# BIRDS4_-Y_panel_FM_GUARANI_v3.net
KiCad netlist of a schematic drawn in EAGLE
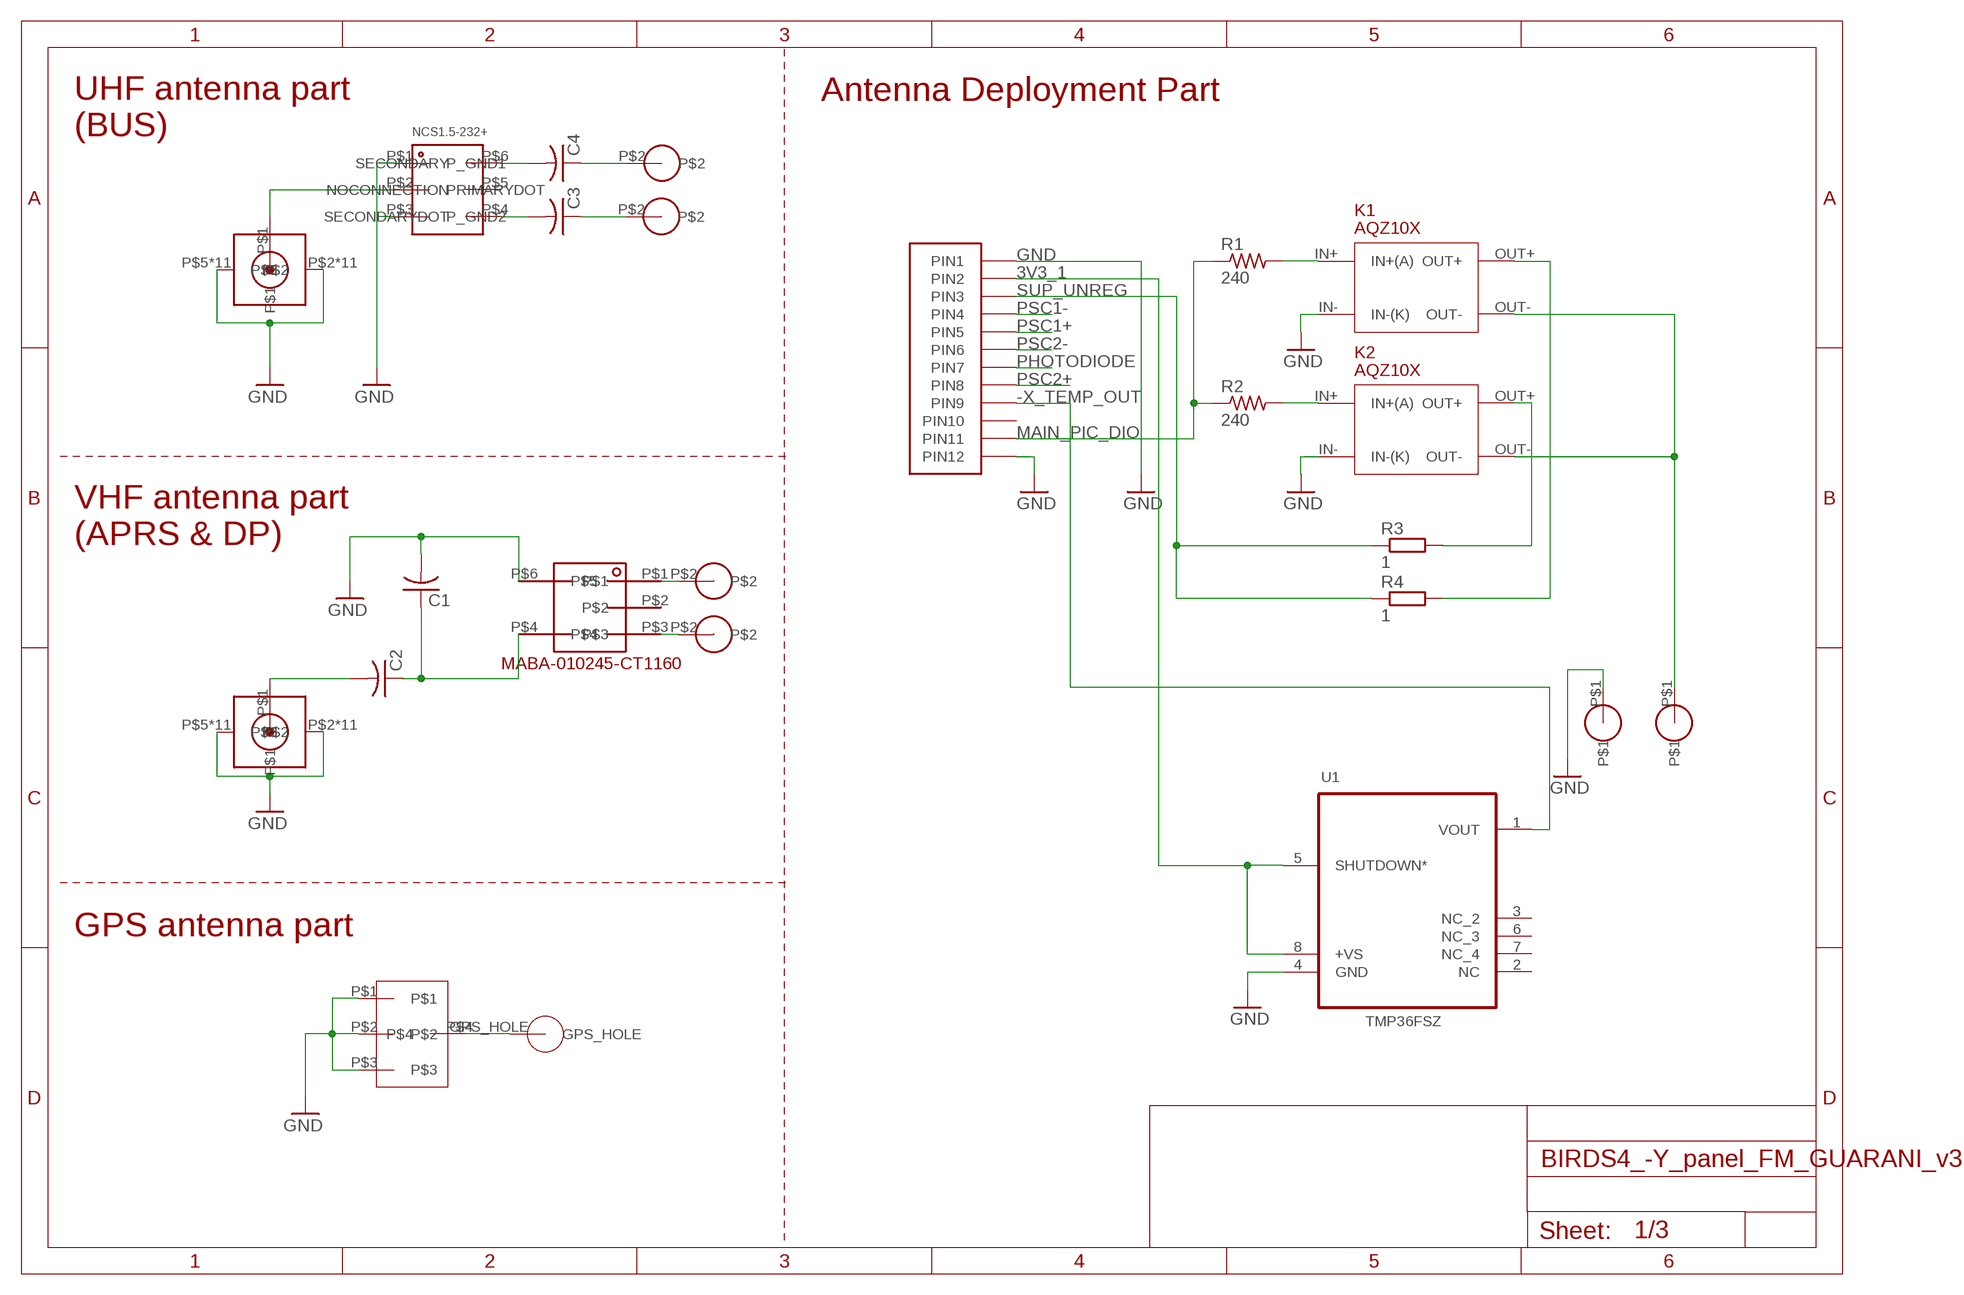
[diagram p0: schematic, sheet 1]
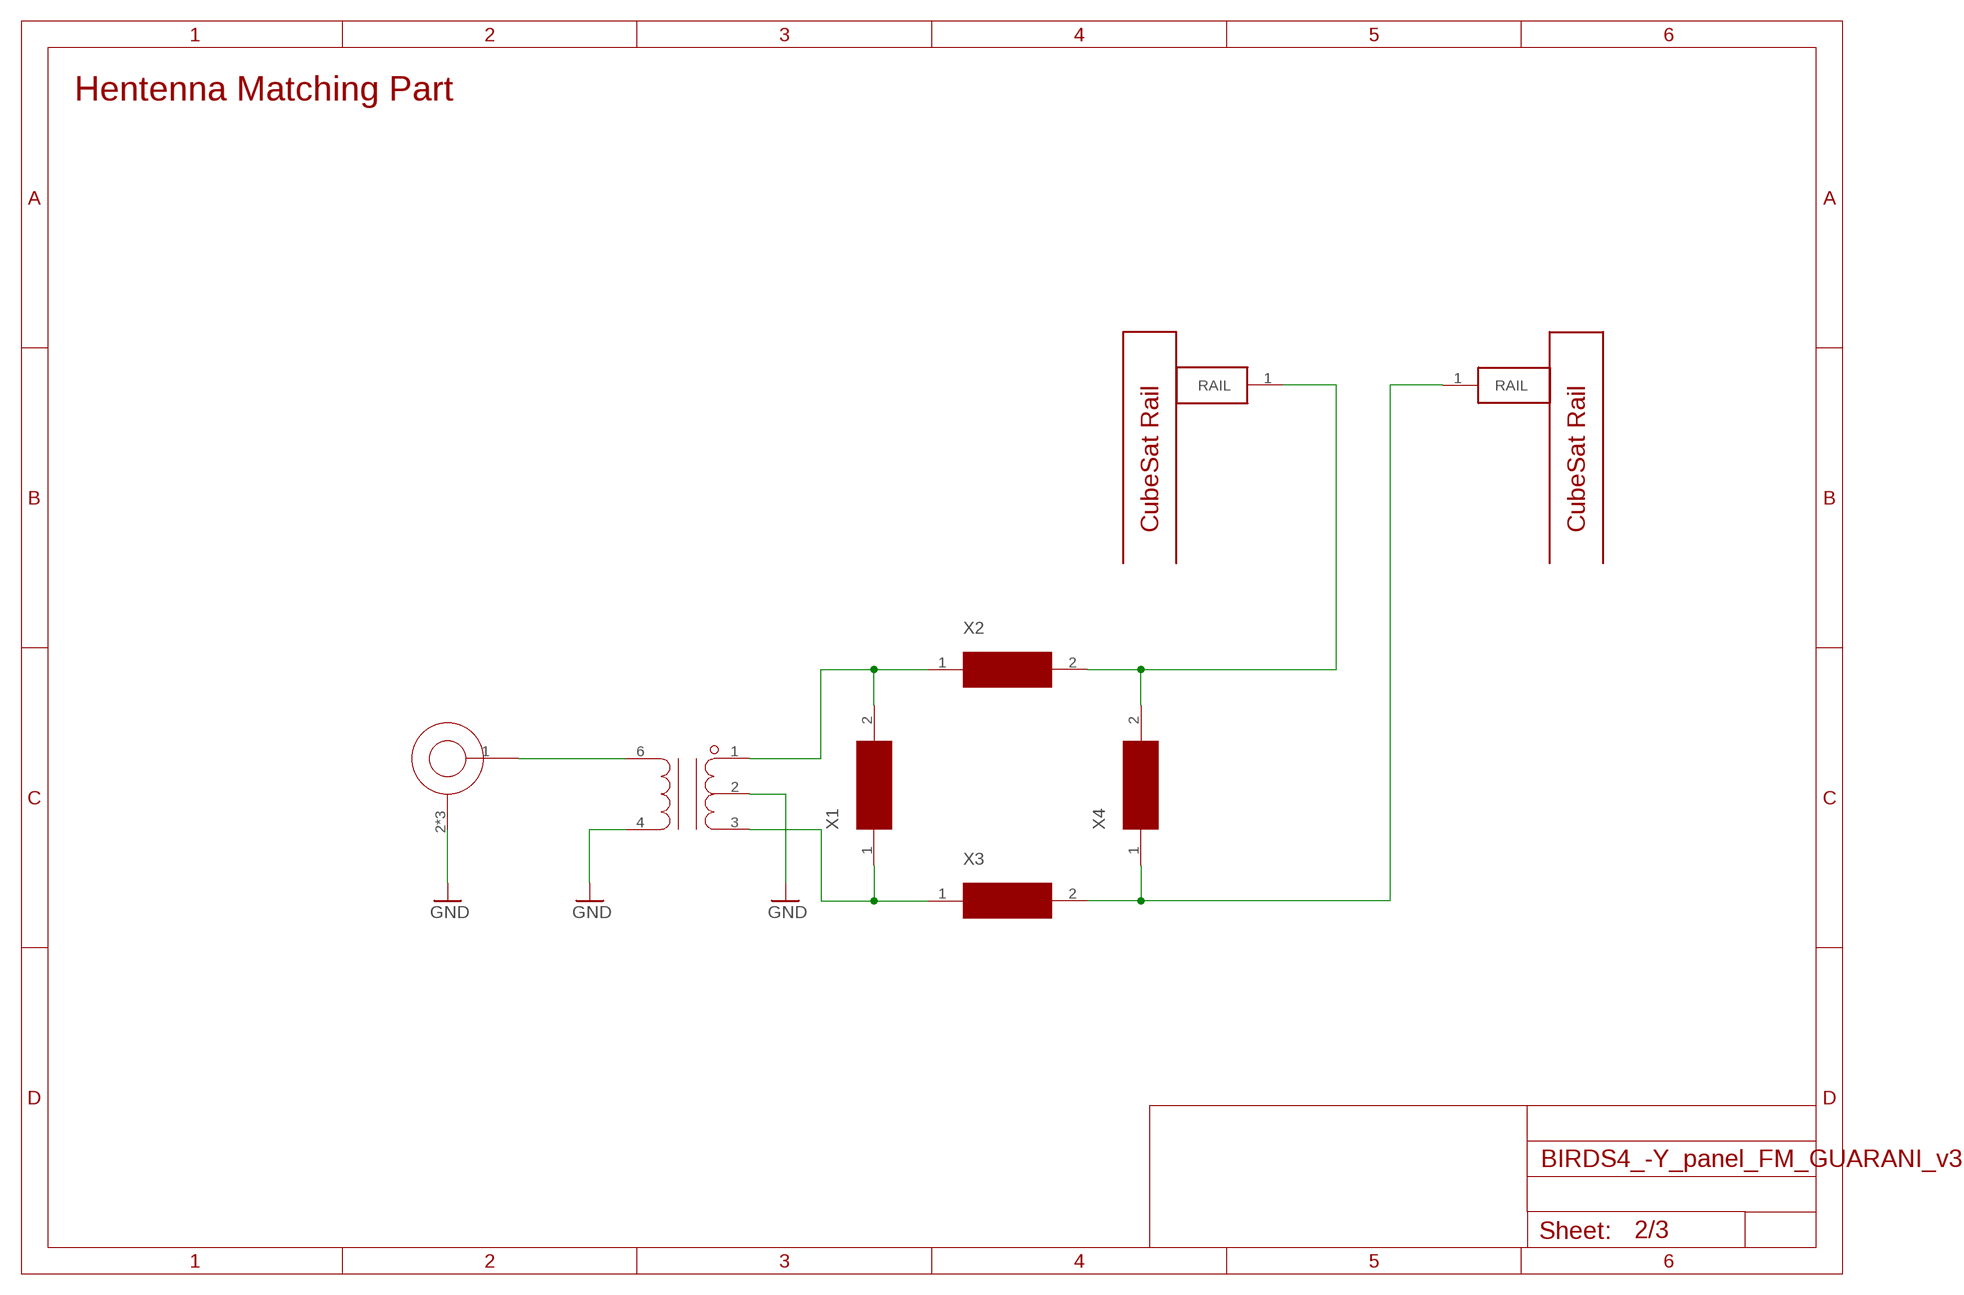
[diagram p1: schematic, sheet 2]
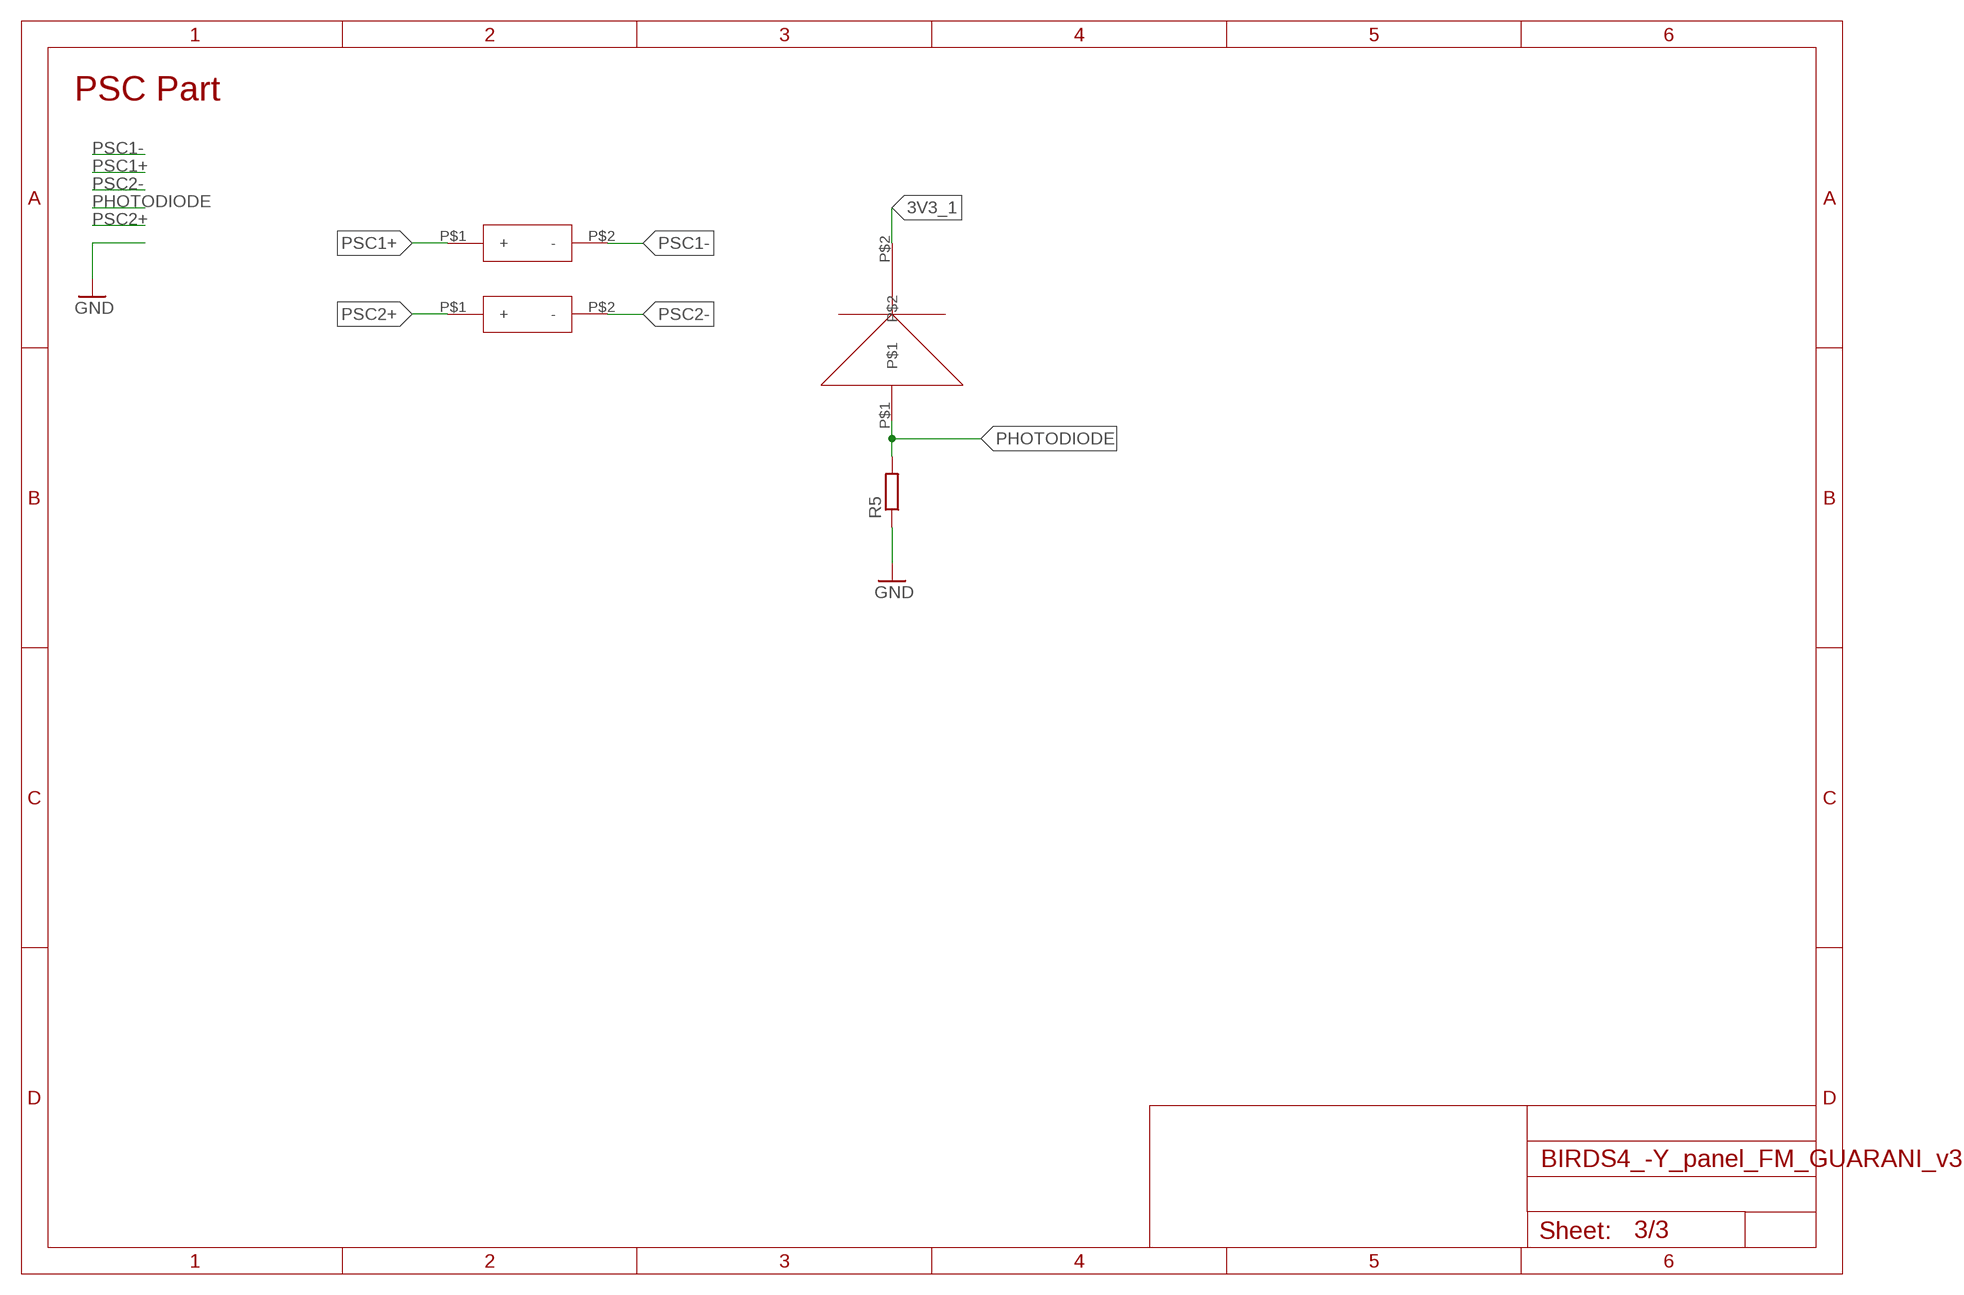
[diagram p2: schematic, sheet 3]

(export (version "E")
  (design (tool "Eeschema 10.0.6"))
  (components
    (comp (ref "C1")
      (value "C-USC1608")
      (footprint "eagle-import:C1608")
      (libsource (lib "eagle-import") (part "C-USC1608"))
    )
    (comp (ref "C2")
      (value "C-USC1608")
      (footprint "eagle-import:C1608")
      (libsource (lib "eagle-import") (part "C-USC1608"))
    )
    (comp (ref "C3")
      (value "C-USC1608")
      (footprint "eagle-import:C1608")
      (libsource (lib "eagle-import") (part "C-USC1608"))
    )
    (comp (ref "C4")
      (value "C-USC1608")
      (footprint "eagle-import:C1608")
      (libsource (lib "eagle-import") (part "C-USC1608"))
    )
    (comp (ref "HOLE1")
      (value "B4_FOR_NEW_DIPOLE")
      (footprint "eagle-import:B4_FOR_NEW_DIPOLE")
      (libsource (lib "eagle-import") (part "B4_FOR_NEW_DIPOLE"))
    )
    (comp (ref "HOLE2")
      (value "B4_FOR_NEW_DIPOLE")
      (footprint "eagle-import:B4_FOR_NEW_DIPOLE")
      (libsource (lib "eagle-import") (part "B4_FOR_NEW_DIPOLE"))
    )
    (comp (ref "HOLE7")
      (value "GPS_HOLE")
      (footprint "eagle-import:GPS_HOLE")
      (libsource (lib "eagle-import") (part "GPS_HOLE"))
    )
    (comp (ref "J1")
      (value "SMA_142_0711_301")
      (footprint "eagle-import:SMA_142_0711_301")
      (libsource (lib "eagle-import") (part "SMA_142_0711_301"))
    )
    (comp (ref "J2")
      (value "SMA_142_0711_301")
      (footprint "eagle-import:SMA_142_0711_301")
      (libsource (lib "eagle-import") (part "SMA_142_0711_301"))
    )
    (comp (ref "J3")
      (value "MMCX_GPS")
      (footprint "eagle-import:MMCX_GPS")
      (libsource (lib "eagle-import") (part "MMCX_GPS"))
    )
    (comp (ref "J5")
      (value "HEADER12PIN")
      (footprint "eagle-import:HEADER12PIN")
      (fields (field (name "SPICEPREFIX") "X"))
      (libsource (lib "eagle-import") (part "HEADER12PIN"))
    )
    (comp (ref "K1")
      (value "AQZ10X")
      (footprint "eagle-import:AQZ10X")
      (libsource (lib "eagle-import") (part "AQZ10X"))
    )
    (comp (ref "K2")
      (value "AQZ10X")
      (footprint "eagle-import:AQZ10X")
      (libsource (lib "eagle-import") (part "AQZ10X"))
    )
    (comp (ref "NCS1")
      (value "NCS1.5-232+")
      (footprint "eagle-import:NCS1.5-232+")
      (libsource (lib "eagle-import") (part "NCS1.5-232+"))
    )
    (comp (ref "R1")
      (value "240")
      (footprint "eagle-import:R0402")
      (libsource (lib "eagle-import") (part "R-US_R0402"))
    )
    (comp (ref "R2")
      (value "240")
      (footprint "eagle-import:R0402")
      (libsource (lib "eagle-import") (part "R-US_R0402"))
    )
    (comp (ref "R3")
      (value "1")
      (footprint "eagle-import:R1218")
      (libsource (lib "eagle-import") (part "R-EU_R1218"))
    )
    (comp (ref "R4")
      (value "1")
      (footprint "eagle-import:R1218")
      (libsource (lib "eagle-import") (part "R-EU_R1218"))
    )
    (comp (ref "U$1")
      (value "NICR_HOLE")
      (footprint "eagle-import:NICR_HOLE")
      (libsource (lib "eagle-import") (part "NICR_HOLE"))
    )
    (comp (ref "U$2")
      (value "MABA-010245-CT1160")
      (footprint "eagle-import:MABA-010245-CT1160")
      (libsource (lib "eagle-import") (part "MABA-010245-CT1160"))
    )
    (comp (ref "U$3")
      (value "B4_FOR_NEW_DIPOLE")
      (footprint "eagle-import:B4_FOR_NEW_DIPOLE")
      (libsource (lib "eagle-import") (part "B4_FOR_NEW_DIPOLE"))
    )
    (comp (ref "U$4")
      (value "B4_FOR_NEW_DIPOLE")
      (footprint "eagle-import:B4_FOR_NEW_DIPOLE")
      (libsource (lib "eagle-import") (part "B4_FOR_NEW_DIPOLE"))
    )
    (comp (ref "U$5")
      (value "NICR_HOLE")
      (footprint "eagle-import:NICR_HOLE")
      (libsource (lib "eagle-import") (part "NICR_HOLE"))
    )
    (comp (ref "U1")
      (value "TMP36FSZ")
      (footprint "eagle-import:SOIC_N")
      (libsource (lib "eagle-import") (part "TMP36FSZ"))
    )
    (comp (ref "HOLE8")
      (value "CUBESAT_RAIL")
      (footprint "eagle-import:HOLE")
      (libsource (lib "eagle-import") (part "CUBESAT_RAIL"))
    )
    (comp (ref "HOLE9")
      (value "CUBESAT_RAIL")
      (footprint "eagle-import:HOLE")
      (libsource (lib "eagle-import") (part "CUBESAT_RAIL"))
    )
    (comp (ref "J4")
      (value "HNT RF CON")
      (footprint "eagle-import:R302302000")
      (fields
        (field (name "MANUFACTURER_PART_NUMBER") "R302302000")
        (field (name "RS_PART_NUMBER") "1250330")
      )
      (libsource (lib "eagle-import") (part "R302302000"))
    )
    (comp (ref "T3")
      (value "TC1-1T+")
      (footprint "eagle-import:TC1.5-52T+")
      (libsource (lib "eagle-import") (part "TC1-1T+"))
    )
    (comp (ref "X1")
      (value "PASSIVECOMPONENT1608")
      (footprint "eagle-import:C1608")
      (libsource (lib "eagle-import") (part "PASSIVECOMPONENT1608"))
    )
    (comp (ref "X2")
      (value "PASSIVECOMPONENT1608")
      (footprint "eagle-import:C1608")
      (libsource (lib "eagle-import") (part "PASSIVECOMPONENT1608"))
    )
    (comp (ref "X3")
      (value "PASSIVECOMPONENT1608")
      (footprint "eagle-import:C1608")
      (libsource (lib "eagle-import") (part "PASSIVECOMPONENT1608"))
    )
    (comp (ref "X4")
      (value "PASSIVECOMPONENT1608")
      (footprint "eagle-import:C1608")
      (libsource (lib "eagle-import") (part "PASSIVECOMPONENT1608"))
    )
    (comp (ref "D1")
      (value "SFH2430")
      (footprint "eagle-import:SFH2430")
      (libsource (lib "eagle-import") (part "SFH2430"))
    )
    (comp (ref "R5")
      (value "R-EU_R0805")
      (footprint "eagle-import:R0805")
      (libsource (lib "eagle-import") (part "R-EU_R0805"))
    )
    (comp (ref "S1")
      (value "PEROVSKITE")
      (footprint "eagle-import:PEROVSKITE")
      (libsource (lib "eagle-import") (part "PEROVSKITE"))
    )
    (comp (ref "S2")
      (value "PEROVSKITE")
      (footprint "eagle-import:PEROVSKITE")
      (libsource (lib "eagle-import") (part "PEROVSKITE"))
    )
  )
  (nets
    (net (code "1") (name "-X_TEMP_OUT") (class "Default")
      (node (ref "J5") (pin "P9") (pinfunction "PIN9_P9") (pintype "bidirectional"))
      (node (ref "U1") (pin "1") (pinfunction "VOUT_1") (pintype "passive"))
    )
    (net (code "2") (name "3V3_1") (class "Default")
      (node (ref "D1") (pin "P$2") (pinfunction "P$2_P$2") (pintype "bidirectional"))
      (node (ref "J5") (pin "P2") (pinfunction "PIN2_P2") (pintype "bidirectional"))
      (node (ref "U1") (pin "5") (pinfunction "SHUTDOWN*_5") (pintype "passive"))
      (node (ref "U1") (pin "8") (pinfunction "+VS_8") (pintype "power_in"))
    )
    (net (code "3") (name "GND") (class "Default")
      (node (ref "C1") (pin "2") (pinfunction "2_2") (pintype "passive"))
      (node (ref "J1") (pin "P$10") (pinfunction "P$3_P$10") (pintype "bidirectional"))
      (node (ref "J1") (pin "P$11") (pinfunction "P$3_P$11") (pintype "bidirectional"))
      (node (ref "J1") (pin "P$12") (pinfunction "P$2_P$12") (pintype "bidirectional"))
      (node (ref "J1") (pin "P$13") (pinfunction "P$2_P$13") (pintype "bidirectional"))
      (node (ref "J1") (pin "P$14") (pinfunction "P$3_P$14") (pintype "bidirectional"))
      (node (ref "J1") (pin "P$15") (pinfunction "P$3_P$15") (pintype "bidirectional"))
      (node (ref "J1") (pin "P$16") (pinfunction "P$2_P$16") (pintype "bidirectional"))
      (node (ref "J1") (pin "P$17") (pinfunction "P$2_P$17") (pintype "bidirectional"))
      (node (ref "J1") (pin "P$18") (pinfunction "P$3_P$18") (pintype "bidirectional"))
      (node (ref "J1") (pin "P$19") (pinfunction "P$3_P$19") (pintype "bidirectional"))
      (node (ref "J1") (pin "P$2") (pinfunction "P$2_P$2") (pintype "bidirectional"))
      (node (ref "J1") (pin "P$20") (pinfunction "P$2_P$20") (pintype "bidirectional"))
      (node (ref "J1") (pin "P$21") (pinfunction "P$2_P$21") (pintype "bidirectional"))
      (node (ref "J1") (pin "P$22") (pinfunction "P$3_P$22") (pintype "bidirectional"))
      (node (ref "J1") (pin "P$23") (pinfunction "P$3_P$23") (pintype "bidirectional"))
      (node (ref "J1") (pin "P$3") (pinfunction "P$2_P$3") (pintype "bidirectional"))
      (node (ref "J1") (pin "P$4") (pinfunction "P$2_P$4") (pintype "bidirectional"))
      (node (ref "J1") (pin "P$5") (pinfunction "P$3_P$5") (pintype "bidirectional"))
      (node (ref "J1") (pin "P$6") (pinfunction "P$3_P$6") (pintype "bidirectional"))
      (node (ref "J1") (pin "P$7") (pinfunction "P$3_P$7") (pintype "bidirectional"))
      (node (ref "J1") (pin "P$8") (pinfunction "P$2_P$8") (pintype "bidirectional"))
      (node (ref "J1") (pin "P$9") (pinfunction "P$2_P$9") (pintype "bidirectional"))
      (node (ref "J2") (pin "P$10") (pinfunction "P$3_P$10") (pintype "bidirectional"))
      (node (ref "J2") (pin "P$11") (pinfunction "P$3_P$11") (pintype "bidirectional"))
      (node (ref "J2") (pin "P$12") (pinfunction "P$2_P$12") (pintype "bidirectional"))
      (node (ref "J2") (pin "P$13") (pinfunction "P$2_P$13") (pintype "bidirectional"))
      (node (ref "J2") (pin "P$14") (pinfunction "P$3_P$14") (pintype "bidirectional"))
      (node (ref "J2") (pin "P$15") (pinfunction "P$3_P$15") (pintype "bidirectional"))
      (node (ref "J2") (pin "P$16") (pinfunction "P$2_P$16") (pintype "bidirectional"))
      (node (ref "J2") (pin "P$17") (pinfunction "P$2_P$17") (pintype "bidirectional"))
      (node (ref "J2") (pin "P$18") (pinfunction "P$3_P$18") (pintype "bidirectional"))
      (node (ref "J2") (pin "P$19") (pinfunction "P$3_P$19") (pintype "bidirectional"))
      (node (ref "J2") (pin "P$2") (pinfunction "P$2_P$2") (pintype "bidirectional"))
      (node (ref "J2") (pin "P$20") (pinfunction "P$2_P$20") (pintype "bidirectional"))
      (node (ref "J2") (pin "P$21") (pinfunction "P$2_P$21") (pintype "bidirectional"))
      (node (ref "J2") (pin "P$22") (pinfunction "P$3_P$22") (pintype "bidirectional"))
      (node (ref "J2") (pin "P$23") (pinfunction "P$3_P$23") (pintype "bidirectional"))
      (node (ref "J2") (pin "P$3") (pinfunction "P$2_P$3") (pintype "bidirectional"))
      (node (ref "J2") (pin "P$4") (pinfunction "P$2_P$4") (pintype "bidirectional"))
      (node (ref "J2") (pin "P$5") (pinfunction "P$3_P$5") (pintype "bidirectional"))
      (node (ref "J2") (pin "P$6") (pinfunction "P$3_P$6") (pintype "bidirectional"))
      (node (ref "J2") (pin "P$7") (pinfunction "P$3_P$7") (pintype "bidirectional"))
      (node (ref "J2") (pin "P$8") (pinfunction "P$2_P$8") (pintype "bidirectional"))
      (node (ref "J2") (pin "P$9") (pinfunction "P$2_P$9") (pintype "bidirectional"))
      (node (ref "J3") (pin "P$1") (pinfunction "P$1_P$1") (pintype "bidirectional"))
      (node (ref "J3") (pin "P$2") (pinfunction "P$2_P$2") (pintype "bidirectional"))
      (node (ref "J3") (pin "P$3") (pinfunction "P$3_P$3") (pintype "bidirectional"))
      (node (ref "J4") (pin "2") (pinfunction "GND_2") (pintype "bidirectional"))
      (node (ref "J4") (pin "3") (pinfunction "GND_3") (pintype "bidirectional"))
      (node (ref "J4") (pin "4") (pinfunction "GND_4") (pintype "bidirectional"))
      (node (ref "J5") (pin "P1") (pinfunction "PIN1_P1") (pintype "bidirectional"))
      (node (ref "J5") (pin "P12") (pinfunction "PIN12_P12") (pintype "bidirectional"))
      (node (ref "K1") (pin "IN-") (pinfunction "IN-(K)_IN-") (pintype "bidirectional"))
      (node (ref "K2") (pin "IN-") (pinfunction "IN-(K)_IN-") (pintype "bidirectional"))
      (node (ref "NCS1") (pin "P$1") (pinfunction "P_GND1_P$1") (pintype "bidirectional"))
      (node (ref "NCS1") (pin "P$3") (pinfunction "P_GND2_P$3") (pintype "bidirectional"))
      (node (ref "R5") (pin "1") (pinfunction "1_1") (pintype "passive"))
      (node (ref "T3") (pin "2") (pinfunction "P$2_2") (pintype "bidirectional"))
      (node (ref "T3") (pin "4") (pinfunction "P$4_4") (pintype "bidirectional"))
      (node (ref "U$2") (pin "P$6") (pinfunction "P$5_P$6") (pintype "bidirectional"))
      (node (ref "U$5") (pin "P$1") (pinfunction "P$1_P$1") (pintype "bidirectional"))
      (node (ref "U1") (pin "4") (pinfunction "GND_4") (pintype "passive"))
    )
    (net (code "4") (name "MAIN_PIC_DIO") (class "Default")
      (node (ref "J5") (pin "P11") (pinfunction "PIN11_P11") (pintype "bidirectional"))
      (node (ref "R1") (pin "1") (pinfunction "1_1") (pintype "passive"))
      (node (ref "R2") (pin "1") (pinfunction "1_1") (pintype "passive"))
    )
    (net (code "5") (name "Net-(C1-Pad1)") (class "Default")
      (node (ref "C1") (pin "1") (pinfunction "1_1") (pintype "passive"))
      (node (ref "C2") (pin "1") (pinfunction "1_1") (pintype "passive"))
      (node (ref "U$2") (pin "P$4") (pinfunction "P$4_P$4") (pintype "bidirectional"))
    )
    (net (code "6") (name "Net-(C2-Pad2)") (class "Default")
      (node (ref "C2") (pin "2") (pinfunction "2_2") (pintype "passive"))
      (node (ref "J2") (pin "P$1") (pinfunction "P$1_P$1") (pintype "bidirectional"))
    )
    (net (code "7") (name "Net-(C3-Pad1)") (class "Default")
      (node (ref "C3") (pin "1") (pinfunction "1_1") (pintype "passive"))
      (node (ref "HOLE1") (pin "P$2") (pinfunction "P$2_P$2") (pintype "bidirectional"))
    )
    (net (code "8") (name "Net-(C4-Pad1)") (class "Default")
      (node (ref "C4") (pin "1") (pinfunction "1_1") (pintype "passive"))
      (node (ref "HOLE2") (pin "P$2") (pinfunction "P$2_P$2") (pintype "bidirectional"))
    )
    (net (code "9") (name "Net-(HOLE7-PadGPS_HOLE)") (class "Default")
      (node (ref "HOLE7") (pin "GPS_HOLE") (pinfunction "GPS_HOLE_GPS_HOLE") (pintype "bidirectional"))
      (node (ref "J3") (pin "P$4") (pinfunction "P$4_P$4") (pintype "bidirectional"))
    )
    (net (code "10") (name "Net-(HOLE8-RAIL)") (class "Default")
      (node (ref "HOLE8") (pin "1") (pinfunction "RAIL_1") (pintype "bidirectional"))
      (node (ref "X2") (pin "2") (pinfunction "P$2_2") (pintype "bidirectional"))
      (node (ref "X4") (pin "2") (pinfunction "P$2_2") (pintype "bidirectional"))
    )
    (net (code "11") (name "Net-(HOLE9-RAIL)") (class "Default")
      (node (ref "HOLE9") (pin "1") (pinfunction "RAIL_1") (pintype "bidirectional"))
      (node (ref "X3") (pin "2") (pinfunction "P$2_2") (pintype "bidirectional"))
      (node (ref "X4") (pin "1") (pinfunction "P$1_1") (pintype "bidirectional"))
    )
    (net (code "12") (name "Net-(J4-LINE)") (class "Default")
      (node (ref "J4") (pin "1") (pinfunction "LINE_1") (pintype "bidirectional"))
      (node (ref "T3") (pin "6") (pinfunction "P$5_6") (pintype "bidirectional"))
    )
    (net (code "13") (name "Net-(K1-IN+(A))") (class "Default")
      (node (ref "K1") (pin "IN+") (pinfunction "IN+(A)_IN+") (pintype "bidirectional"))
      (node (ref "R1") (pin "2") (pinfunction "2_2") (pintype "passive"))
    )
    (net (code "14") (name "Net-(K1-PadOUT+)") (class "Default")
      (node (ref "K1") (pin "OUT+") (pinfunction "OUT+_OUT+") (pintype "bidirectional"))
      (node (ref "R4") (pin "2") (pinfunction "2_2") (pintype "passive"))
    )
    (net (code "15") (name "Net-(K1-PadOUT-)") (class "Default")
      (node (ref "K1") (pin "OUT-") (pinfunction "OUT-_OUT-") (pintype "bidirectional"))
      (node (ref "K2") (pin "OUT-") (pinfunction "OUT-_OUT-") (pintype "bidirectional"))
      (node (ref "U$1") (pin "P$1") (pinfunction "P$1_P$1") (pintype "bidirectional"))
    )
    (net (code "16") (name "Net-(K2-IN+(A))") (class "Default")
      (node (ref "K2") (pin "IN+") (pinfunction "IN+(A)_IN+") (pintype "bidirectional"))
      (node (ref "R2") (pin "2") (pinfunction "2_2") (pintype "passive"))
    )
    (net (code "17") (name "Net-(K2-PadOUT+)") (class "Default")
      (node (ref "K2") (pin "OUT+") (pinfunction "OUT+_OUT+") (pintype "bidirectional"))
      (node (ref "R3") (pin "2") (pinfunction "2_2") (pintype "passive"))
    )
    (net (code "18") (name "Net-(NCS1-PRIMARYDOT)") (class "Default")
      (node (ref "J1") (pin "P$1") (pinfunction "P$1_P$1") (pintype "bidirectional"))
      (node (ref "NCS1") (pin "P$2") (pinfunction "PRIMARYDOT_P$2") (pintype "bidirectional"))
    )
    (net (code "19") (name "Net-(NCS1-SECONDARY)") (class "Default")
      (node (ref "C4") (pin "2") (pinfunction "2_2") (pintype "passive"))
      (node (ref "NCS1") (pin "P$6") (pinfunction "SECONDARY_P$6") (pintype "bidirectional"))
    )
    (net (code "20") (name "Net-(NCS1-SECONDARYDOT)") (class "Default")
      (node (ref "C3") (pin "2") (pinfunction "2_2") (pintype "passive"))
      (node (ref "NCS1") (pin "P$4") (pinfunction "SECONDARYDOT_P$4") (pintype "bidirectional"))
    )
    (net (code "21") (name "Net-(T3-P$1)") (class "Default")
      (node (ref "T3") (pin "1") (pinfunction "P$1_1") (pintype "bidirectional"))
      (node (ref "X1") (pin "2") (pinfunction "P$2_2") (pintype "bidirectional"))
      (node (ref "X2") (pin "1") (pinfunction "P$1_1") (pintype "bidirectional"))
    )
    (net (code "22") (name "Net-(T3-P$3)") (class "Default")
      (node (ref "T3") (pin "3") (pinfunction "P$3_3") (pintype "bidirectional"))
      (node (ref "X1") (pin "1") (pinfunction "P$1_1") (pintype "bidirectional"))
      (node (ref "X3") (pin "1") (pinfunction "P$1_1") (pintype "bidirectional"))
    )
    (net (code "23") (name "Net-(U$2-PadP$1)") (class "Default")
      (node (ref "U$2") (pin "P$1") (pinfunction "P$1_P$1") (pintype "bidirectional"))
      (node (ref "U$3") (pin "P$2") (pinfunction "P$2_P$2") (pintype "bidirectional"))
    )
    (net (code "24") (name "Net-(U$2-PadP$3)") (class "Default")
      (node (ref "U$2") (pin "P$3") (pinfunction "P$3_P$3") (pintype "bidirectional"))
      (node (ref "U$4") (pin "P$2") (pinfunction "P$2_P$2") (pintype "bidirectional"))
    )
    (net (code "25") (name "PHOTODIODE") (class "Default")
      (node (ref "D1") (pin "P$1") (pinfunction "P$1_P$1") (pintype "bidirectional"))
      (node (ref "J5") (pin "P7") (pinfunction "PIN7_P7") (pintype "bidirectional"))
      (node (ref "R5") (pin "2") (pinfunction "2_2") (pintype "passive"))
    )
    (net (code "26") (name "PSC1+") (class "Default")
      (node (ref "J5") (pin "P5") (pinfunction "PIN5_P5") (pintype "bidirectional"))
      (node (ref "S1") (pin "P$1") (pinfunction "+_P$1") (pintype "bidirectional"))
    )
    (net (code "27") (name "PSC1-") (class "Default")
      (node (ref "J5") (pin "P4") (pinfunction "PIN4_P4") (pintype "bidirectional"))
      (node (ref "S1") (pin "P$2") (pinfunction "-_P$2") (pintype "bidirectional"))
    )
    (net (code "28") (name "PSC2+") (class "Default")
      (node (ref "J5") (pin "P8") (pinfunction "PIN8_P8") (pintype "bidirectional"))
      (node (ref "S2") (pin "P$1") (pinfunction "+_P$1") (pintype "bidirectional"))
    )
    (net (code "29") (name "PSC2-") (class "Default")
      (node (ref "J5") (pin "P6") (pinfunction "PIN6_P6") (pintype "bidirectional"))
      (node (ref "S2") (pin "P$2") (pinfunction "-_P$2") (pintype "bidirectional"))
    )
    (net (code "30") (name "SUP_UNREG") (class "Default")
      (node (ref "J5") (pin "P3") (pinfunction "PIN3_P3") (pintype "bidirectional"))
      (node (ref "R3") (pin "1") (pinfunction "1_1") (pintype "passive"))
      (node (ref "R4") (pin "1") (pinfunction "1_1") (pintype "passive"))
    )
    (net (code "31") (name "unconnected-(J5-PIN10-PadP10)") (class "Default")
      (node (ref "J5") (pin "P10") (pinfunction "PIN10_P10") (pintype "bidirectional"))
    )
    (net (code "32") (name "unconnected-(NCS1-NOCONNECTION-PadP$5)") (class "Default")
      (node (ref "NCS1") (pin "P$5") (pinfunction "NOCONNECTION_P$5") (pintype "bidirectional"))
    )
    (net (code "33") (name "unconnected-(U$2-PadP$2)") (class "Default")
      (node (ref "U$2") (pin "P$2") (pinfunction "P$2_P$2") (pintype "bidirectional"))
    )
    (net (code "34") (name "unconnected-(U1-NC-Pad2)") (class "Default")
      (node (ref "U1") (pin "2") (pinfunction "NC_2") (pintype "passive"))
    )
    (net (code "35") (name "unconnected-(U1-NC_2-Pad3)") (class "Default")
      (node (ref "U1") (pin "3") (pinfunction "NC_2_3") (pintype "passive"))
    )
    (net (code "36") (name "unconnected-(U1-NC_3-Pad6)") (class "Default")
      (node (ref "U1") (pin "6") (pinfunction "NC_3_6") (pintype "passive"))
    )
    (net (code "37") (name "unconnected-(U1-NC_4-Pad7)") (class "Default")
      (node (ref "U1") (pin "7") (pinfunction "NC_4_7") (pintype "passive"))
    )
  )
)
